# power_side.net
KiCad netlist of a schematic drawn in Altium Designer
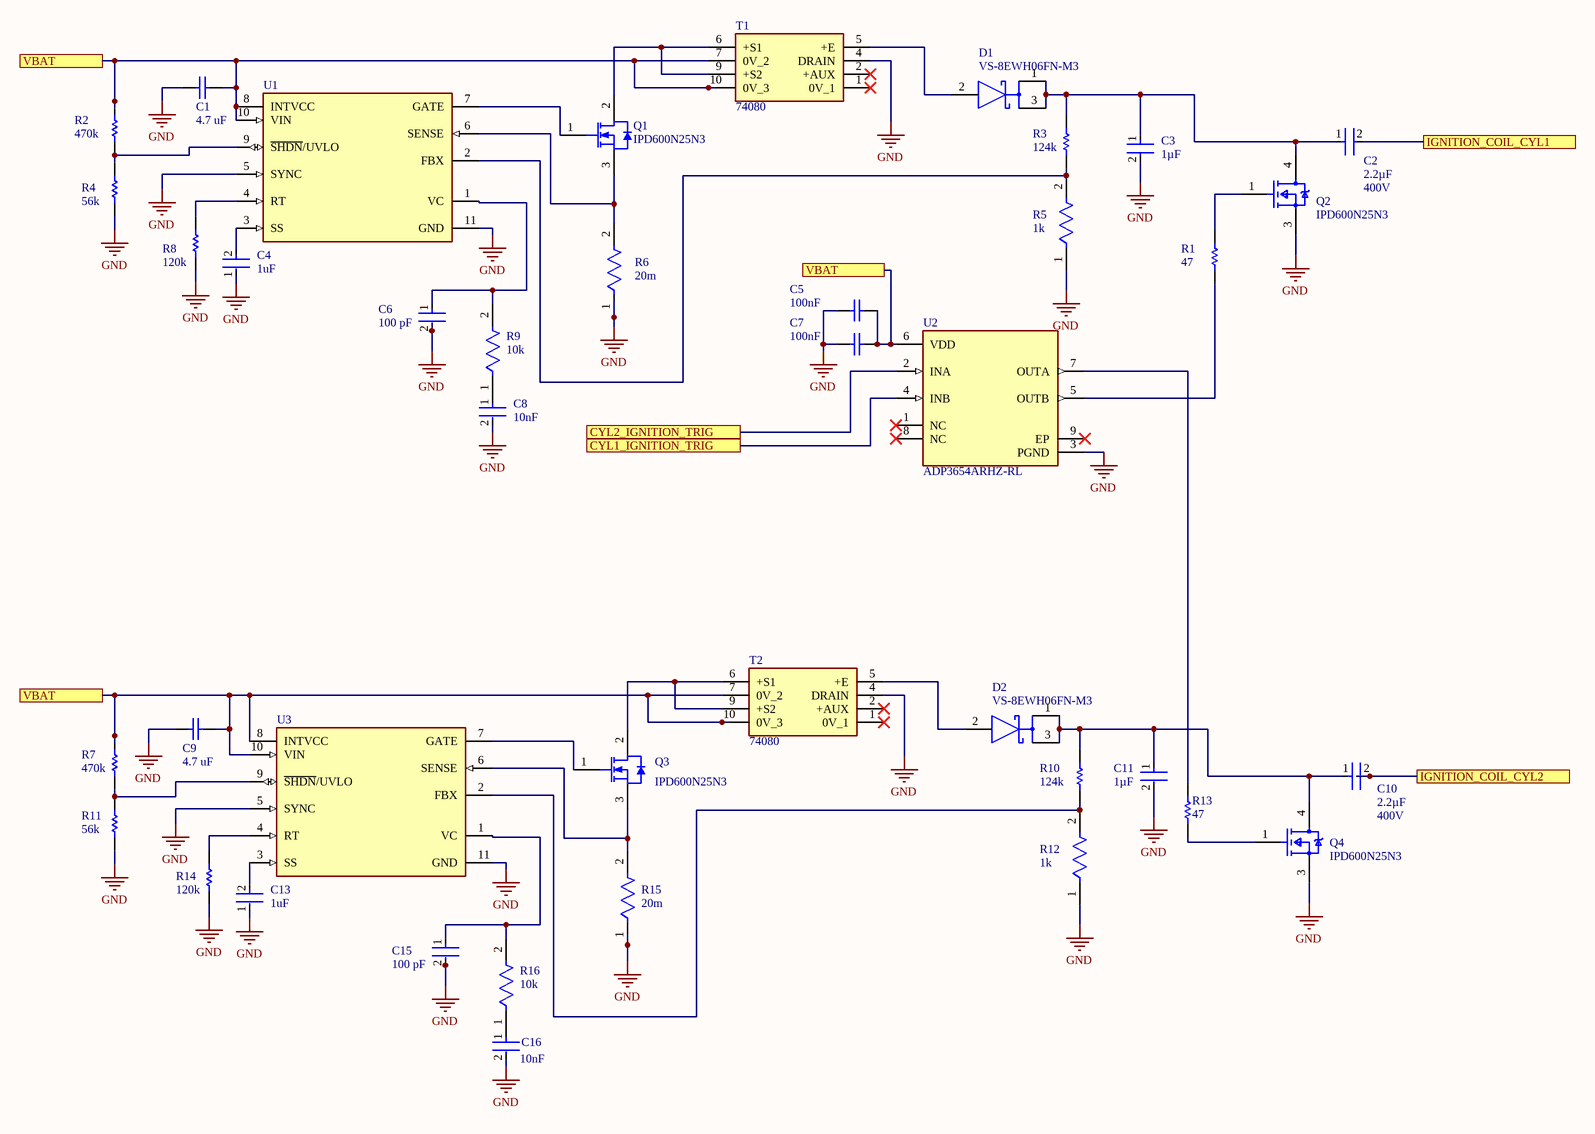
[diagram p0: power_side.SchDoc]

(export (version "E")
  (design (tool "Eeschema 10.0.6"))
  (components
    (comp (ref "C1")
      (value "GRM21BR61C475KA88L")
      (footprint "CAPC2013X135X45LL10T25")
      (description "Chip Capacitor, 4.7 uF, +/- 10%, 16 V, -55 to 85 degC, 0805 (2012 Metric), RoHS, Tape and Reel")
      (fields (field (name "TOLERANCE") "10%") (field (name "CAPACITANCE") "4.7 uF"))
      (libsource (lib "Altium Content Vault") (part "CAP-NP-2"))
    )
    (comp (ref "C2")
      (value "BFC233820225")
      (footprint "FP-BFC233820225-MFG")
      (description "BFC233820225 Film Capacitor, Polypropylene, 800V, 20% +Tol, 20% -Tol, 0.22uF, Through Hole Mount")
      (fields
        (field (name "VOLTAGE RATING (AC)") "400V")
        (field (name "CAPACITANCE") "2.2µF")
        (field (name "TOLERANCE") "20%")
      )
      (libsource (lib "Altium Content Vault") (part "02cd4be3c70576c341d710602a673aa"))
    )
    (comp (ref "C3")
      (value "B32672Z4105K000")
      (footprint "FP-B32672Z4105K000-MFG")
      (fields (field (name "TOLERANCE") "10%") (field (name "CAPACITANCE") "1µF"))
      (libsource (lib "Altium Content Vault") (part "11868f565c42a9108669ba33697ecf6"))
    )
    (comp (ref "C4")
      (value "C1608X5R1H105K080AB")
      (footprint "FP-C1608-080-0_1-IPC_B")
      (description "Multilayer Ceramic Capacitors 1μF ±10% 50V X5R SMD 0603")
      (fields
        (field (name "VOLTAGE") "50V")
        (field (name "CAPACITANCE") "1uF")
        (field (name "TOLERANCE") "10%")
      )
      (libsource (lib "Altium Content Vault") (part "236180d848d6139a670b325ea6854c9"))
    )
    (comp (ref "C5")
      (value "100nF")
      (footprint "CAPC1608X90X35LL15T15")
      (fields
        (field (name "MANUFACTURER") "AVX Interconnect / Elco")
        (field (name "PART NUMBER") "06035C104KAT4A")
      )
      (libsource (lib "Altium Content Vault") (part "CAP"))
    )
    (comp (ref "C6")
      (value "CC0603KRX7R9BB101")
      (footprint "FP-CC0603-DA-MFG")
      (description "CAP CER 100PF 50V X7R 0603")
      (fields
        (field (name "TOLERANCE") "0.1")
        (field (name "OCTOPART") "https://octopart.com/cc0603krx7r9bb101-yageo-42334526")
        (field (name "CAPACITANCE") "100 pF")
      )
      (libsource (lib "Altium Content Vault") (part "11868f565c42a9108669ba33697ecf6"))
    )
    (comp (ref "C7")
      (value "100nF")
      (footprint "CAPC1608X87X35NL15T15")
      (fields (field (name "PART NUMBER") "C0603C475K8PACTU") (field (name "MANUFACTURER") "Kemet"))
      (libsource (lib "Altium Content Vault") (part "CAP"))
    )
    (comp (ref "C8")
      (value "06035C103KAT2A")
      (footprint "FP-0603-L_1_6_0_15-W_0_81-MFG")
      (description "General Purpose Ceramic Capacitor, 0603, 10nF, 10%, X7R, 15%, 50V")
      (fields
        (field (name "VOLTAGE") "50V")
        (field (name "CAPACITANCE") "10nF")
        (field (name "TOLERANCE") "10%")
      )
      (libsource (lib "Altium Content Vault") (part "02cd4be3c70576c341d710602a673aa"))
    )
    (comp (ref "C9")
      (value "GRM21BR61C475KA88L")
      (footprint "CAPC2013X135X45LL10T25")
      (description "Chip Capacitor, 4.7 uF, +/- 10%, 16 V, -55 to 85 degC, 0805 (2012 Metric), RoHS, Tape and Reel")
      (fields (field (name "TOLERANCE") "10%") (field (name "CAPACITANCE") "4.7 uF"))
      (libsource (lib "Altium Content Vault") (part "CAP-NP-2"))
    )
    (comp (ref "C10")
      (value "BFC233820225")
      (footprint "FP-BFC233820225-MFG")
      (description "BFC233820225 Film Capacitor, Polypropylene, 800V, 20% +Tol, 20% -Tol, 0.22uF, Through Hole Mount")
      (fields
        (field (name "VOLTAGE RATING (AC)") "400V")
        (field (name "CAPACITANCE") "2.2µF")
        (field (name "TOLERANCE") "20%")
      )
      (libsource (lib "Altium Content Vault") (part "02cd4be3c70576c341d710602a673aa"))
    )
    (comp (ref "C11")
      (value "B32672Z4105K000")
      (footprint "FP-B32672Z4105K000-MFG")
      (fields (field (name "TOLERANCE") "10%") (field (name "CAPACITANCE") "1µF"))
      (libsource (lib "Altium Content Vault") (part "11868f565c42a9108669ba33697ecf6"))
    )
    (comp (ref "C13")
      (value "C1608X5R1H105K080AB")
      (footprint "FP-C1608-080-0_1-IPC_B")
      (description "Multilayer Ceramic Capacitors 1μF ±10% 50V X5R SMD 0603")
      (fields
        (field (name "VOLTAGE") "50V")
        (field (name "CAPACITANCE") "1uF")
        (field (name "TOLERANCE") "10%")
      )
      (libsource (lib "Altium Content Vault") (part "236180d848d6139a670b325ea6854c9"))
    )
    (comp (ref "C15")
      (value "CC0603KRX7R9BB101")
      (footprint "FP-CC0603-DA-MFG")
      (description "CAP CER 100PF 50V X7R 0603")
      (fields
        (field (name "TOLERANCE") "0.1")
        (field (name "OCTOPART") "https://octopart.com/cc0603krx7r9bb101-yageo-42334526")
        (field (name "CAPACITANCE") "100 pF")
      )
      (libsource (lib "Altium Content Vault") (part "11868f565c42a9108669ba33697ecf6"))
    )
    (comp (ref "C16")
      (value "06035C103KAT2A")
      (footprint "FP-0603-L_1_6_0_15-W_0_81-MFG")
      (description "General Purpose Ceramic Capacitor, 0603, 10nF, 10%, X7R, 15%, 50V")
      (fields
        (field (name "VOLTAGE") "50V")
        (field (name "CAPACITANCE") "10nF")
        (field (name "TOLERANCE") "10%")
      )
      (libsource (lib "Altium Content Vault") (part "02cd4be3c70576c341d710602a673aa"))
    )
    (comp (ref "D1")
      (value "C3D03060E")
      (footprint "FP-TO-252-2_v2-MFG")
      (description "DIODE SCHOTTKY 600V 3A TO252-2")
      (fields (field (name "PN") "VS-8EWH06FN-M3"))
      (libsource (lib "Altium Content Vault") (part "28d9654e8ecf1b769ed8fe2ca1197a5"))
    )
    (comp (ref "D2")
      (value "C3D03060E")
      (footprint "FP-TO-252-2_v2-MFG")
      (description "DIODE SCHOTTKY 600V 3A TO252-2")
      (fields (field (name "PN") "VS-8EWH06FN-M3"))
      (libsource (lib "Altium Content Vault") (part "28d9654e8ecf1b769ed8fe2ca1197a5"))
    )
    (comp (ref "Q1")
      (value "IPD600N25N3")
      (footprint "INF-PG-TO252-3-11_A_L")
      (fields (field (name "PARTNUMBER") "IPD035N06L3 G") (field (name "MANUFACTURER") "Infineon"))
      (libsource (lib "Altium Content Vault") (part "INF-NEMOS-GDS-3"))
    )
    (comp (ref "Q2")
      (value "IPD600N25N3")
      (footprint "FP-PG-TO252-3-MFG")
      (description "MOSFET N-CH 30V 161A DPAK")
      (fields
        (field (name "OCTOPART") "https://octopart.com/irlr7843trpbf-infineon-65875062")
        (field (name "MANUFACTURER PART NUMBER") "IRLR7843TRPBF")
      )
      (libsource (lib "Altium Content Vault") (part "2f21c11e83d30f418bb422e5a3b3d11"))
    )
    (comp (ref "Q3")
      (value "IPD600N25N3")
      (footprint "INF-PG-TO252-3-11_A_L")
      (fields (field (name "PARTNUMBER") "IPD035N06L3 G") (field (name "MANUFACTURER") "Infineon"))
      (libsource (lib "Altium Content Vault") (part "INF-NEMOS-GDS-3"))
    )
    (comp (ref "Q4")
      (value "IPD600N25N3")
      (footprint "FP-PG-TO252-3-MFG")
      (description "MOSFET N-CH 30V 161A DPAK")
      (fields
        (field (name "OCTOPART") "https://octopart.com/irlr7843trpbf-infineon-65875062")
        (field (name "MANUFACTURER PART NUMBER") "IRLR7843TRPBF")
      )
      (libsource (lib "Altium Content Vault") (part "2f21c11e83d30f418bb422e5a3b3d11"))
    )
    (comp (ref "R1")
      (value "47")
      (footprint "RESC1609X50X30LL10T20")
      (fields (field (name "MANUFACTURER") "Vishay Dale") (field (name "PART NUMBER") "CRCW060347R0FKEA"))
      (libsource (lib "Altium Content Vault") (part "RES"))
    )
    (comp (ref "R2")
      (value "470k")
      (footprint "RESC1608X55X25ML10T15")
      (description "Chip Resistor, 470 KOhm, +/- 1%, 0.1 W, -55 to 155 degC, 0603 (1608 Metric), RoHS, Tape and Reel")
      (fields (field (name "Comment") "RC0603FR-07470KL"))
      (libsource (lib "Altium Content Vault") (part "RES-2"))
    )
    (comp (ref "R3")
      (value "124k")
      (footprint "RESC1608X55X30LL15T15")
      (fields (field (name "PART NUMBER") "ERJ-3EKF1243V") (field (name "MANUFACTURER") "Panasonic"))
      (libsource (lib "Altium Content Vault") (part "RES"))
    )
    (comp (ref "R4")
      (value "56k")
      (footprint "RESC1608X55X25LL10T15")
      (description "Chip Resistor, 56 KOhm, +/- 1%, 0.1 W, -55 to 155 degC, 0603 (1608 Metric), RoHS, Tape and Reel")
      (fields (field (name "MANUFACTURER") "Yageo") (field (name "TOLERANCE") "1%"))
      (libsource (lib "Altium Content Vault") (part "RES-2"))
    )
    (comp (ref "R5")
      (value "1k")
      (footprint "FP-RC0603-0_55-IPC_C")
      (description "RES 1K OHM 1% 1/10W 0603")
      (fields (field (name "TOLERANCE") "1%") (field (name "Comment") "RC0603FR-071KL"))
      (libsource (lib "Altium Content Vault") (part "1029c3af85768c4190bb7ad29bc67b5"))
    )
    (comp (ref "R6")
      (value "20m")
      (footprint "FP-CRA2512-MFG")
      (description "RES 0.02 OHM 1% 3W 2512")
      (fields (field (name "Comment") "CRA2512-FZ-R020ELF"))
      (libsource (lib "Altium Content Vault") (part "1029c3af85768c4190bb7ad29bc67b5"))
    )
    (comp (ref "R7")
      (value "470k")
      (footprint "RESC1608X55X25ML10T15")
      (description "Chip Resistor, 470 KOhm, +/- 1%, 0.1 W, -55 to 155 degC, 0603 (1608 Metric), RoHS, Tape and Reel")
      (fields (field (name "Comment") "RC0603FR-07470KL"))
      (libsource (lib "Altium Content Vault") (part "RES-2"))
    )
    (comp (ref "R8")
      (value "120k")
      (footprint "RESC1608X55X25NL10T15")
      (description "Chip Resistor, 120 KOhm, +/- 1%, 100 mW, -55 to 155 degC, 0603 (1608 Metric), RoHS, Tape and Reel")
      (fields (field (name "TOLERANCE") "10%") (field (name "Comment") "RC0603FR-07120KL"))
      (libsource (lib "Altium Content Vault") (part "RES-2"))
    )
    (comp (ref "R9")
      (value "RC0603FR-0710KL")
      (footprint "FP-RC0603-0_55-IPC_C")
      (description "RES 10K OHM 1% 1/10W 0603")
      (fields (field (name "TOLERANCE") "1%") (field (name "RESISTANCE") "10k"))
      (libsource (lib "Altium Content Vault") (part "1029c3af85768c4190bb7ad29bc67b5"))
    )
    (comp (ref "R10")
      (value "124k")
      (footprint "RESC1608X55X30LL15T15")
      (fields (field (name "PART NUMBER") "ERJ-3EKF1243V") (field (name "MANUFACTURER") "Panasonic"))
      (libsource (lib "Altium Content Vault") (part "RES"))
    )
    (comp (ref "R11")
      (value "RC0603FR-0756KL")
      (footprint "RESC1608X55X25LL10T15")
      (description "Chip Resistor, 56 KOhm, +/- 1%, 0.1 W, -55 to 155 degC, 0603 (1608 Metric), RoHS, Tape and Reel")
      (fields
        (field (name "MANUFACTURER") "Yageo")
        (field (name "RESISTANCE") "56k")
        (field (name "TOLERANCE") "1%")
      )
      (libsource (lib "Altium Content Vault") (part "RES-2"))
    )
    (comp (ref "R12")
      (value "1k")
      (footprint "FP-RC0603-0_55-IPC_C")
      (description "RES 1K OHM 1% 1/10W 0603")
      (fields (field (name "TOLERANCE") "1%") (field (name "Comment") "RC0603FR-071KL"))
      (libsource (lib "Altium Content Vault") (part "1029c3af85768c4190bb7ad29bc67b5"))
    )
    (comp (ref "R13")
      (value "47")
      (footprint "RESC1609X50X30LL10T20")
      (fields (field (name "MANUFACTURER") "Vishay Dale") (field (name "PART NUMBER") "CRCW060347R0FKEA"))
      (libsource (lib "Altium Content Vault") (part "RES"))
    )
    (comp (ref "R14")
      (value "120k")
      (footprint "RESC1608X55X25NL10T15")
      (description "Chip Resistor, 120 KOhm, +/- 1%, 100 mW, -55 to 155 degC, 0603 (1608 Metric), RoHS, Tape and Reel")
      (fields (field (name "TOLERANCE") "10%") (field (name "Comment") "RC0603FR-07120KL"))
      (libsource (lib "Altium Content Vault") (part "RES-2"))
    )
    (comp (ref "R15")
      (value "20m")
      (footprint "FP-CRA2512-MFG")
      (description "RES 0.02 OHM 1% 3W 2512")
      (fields (field (name "Comment") "CRA2512-FZ-R020ELF"))
      (libsource (lib "Altium Content Vault") (part "1029c3af85768c4190bb7ad29bc67b5"))
    )
    (comp (ref "R16")
      (value "RC0603FR-0710KL")
      (footprint "FP-RC0603-0_55-IPC_C")
      (description "RES 10K OHM 1% 1/10W 0603")
      (fields (field (name "TOLERANCE") "1%") (field (name "RESISTANCE") "10k"))
      (libsource (lib "Altium Content Vault") (part "1029c3af85768c4190bb7ad29bc67b5"))
    )
    (comp (ref "T1")
      (value "74080")
      (footprint "SamacSys:74080")
      (description "Transformer")
      (libsource (lib "*") (part "74080"))
    )
    (comp (ref "T2")
      (value "74080")
      (footprint "SamacSys:74080")
      (description "Transformer")
      (libsource (lib "*") (part "74080"))
    )
    (comp (ref "U1")
      (value "LT3758EDD#PBF")
      (footprint "FP-DD-10-05-08-1699-IPC_B")
      (description "IC REG CTRLR MULT TOPOLOGY 10DFN")
      (libsource (lib "Altium Content Vault") (part "079e3863d39c5e5796f69dc810f510e"))
    )
    (comp (ref "U2")
      (value "ADP3654ARHZ-RL")
      (footprint "FP-RH-8-1-IPC_C")
      (description "IC GATE DRVR LOW-SIDE 8MINISOIC")
      (libsource (lib "Altium Content Vault") (part "30ea4086147ff647bd0a3436ecf34e5"))
    )
    (comp (ref "U3")
      (value "LT3758EDD#PBF")
      (footprint "FP-DD-10-05-08-1699-IPC_B")
      (description "IC REG CTRLR MULT TOPOLOGY 10DFN")
      (libsource (lib "Altium Content Vault") (part "079e3863d39c5e5796f69dc810f510e"))
    )
  )
  (nets
    (net (code "1") (name "/CYL1_IGNITION_TRIG") (class "Default")
      (node (ref "U2") (pin "4") (pinfunction "INB_4") (pintype "input"))
    )
    (net (code "2") (name "/CYL2_IGNITION_TRIG") (class "Default")
      (node (ref "U2") (pin "2") (pinfunction "INA_2") (pintype "input"))
    )
    (net (code "3") (name "/IGNITION_COIL_CYL1") (class "Default")
      (node (ref "C2") (pin "2") (pinfunction "2_2") (pintype "passive"))
    )
    (net (code "4") (name "/IGNITION_COIL_CYL2") (class "Default")
      (node (ref "C10") (pin "2") (pinfunction "2_2") (pintype "passive"))
    )
    (net (code "5") (name "/VBAT") (class "Default")
      (node (ref "C1") (pin "2") (pinfunction "2_2") (pintype "passive"))
      (node (ref "C5") (pin "1") (pinfunction "1_1") (pintype "passive"))
      (node (ref "C7") (pin "2") (pinfunction "2_2") (pintype "passive"))
      (node (ref "C9") (pin "2") (pinfunction "2_2") (pintype "passive"))
      (node (ref "R2") (pin "2") (pinfunction "2_2") (pintype "passive"))
      (node (ref "R7") (pin "2") (pinfunction "2_2") (pintype "passive"))
      (node (ref "T1") (pin "10") (pinfunction "0V_3_10") (pintype "passive"))
      (node (ref "T1") (pin "7") (pinfunction "0V_2_7") (pintype "passive"))
      (node (ref "T2") (pin "10") (pinfunction "0V_3_10") (pintype "passive"))
      (node (ref "T2") (pin "7") (pinfunction "0V_2_7") (pintype "passive"))
      (node (ref "U1") (pin "10") (pinfunction "VIN_10") (pintype "input"))
      (node (ref "U1") (pin "8") (pinfunction "INTVCC_8") (pintype "power_in"))
      (node (ref "U2") (pin "6") (pinfunction "VDD_6") (pintype "power_in"))
      (node (ref "U3") (pin "10") (pinfunction "VIN_10") (pintype "input"))
      (node (ref "U3") (pin "8") (pinfunction "INTVCC_8") (pintype "power_in"))
    )
    (net (code "6") (name "GND") (class "Default")
      (node (ref "C1") (pin "1") (pinfunction "1_1") (pintype "passive"))
      (node (ref "C11") (pin "2") (pinfunction "2_2") (pintype "passive"))
      (node (ref "C13") (pin "1") (pinfunction "1_1") (pintype "passive"))
      (node (ref "C15") (pin "2") (pinfunction "2_2") (pintype "passive"))
      (node (ref "C16") (pin "2") (pinfunction "2_2") (pintype "passive"))
      (node (ref "C3") (pin "2") (pinfunction "2_2") (pintype "passive"))
      (node (ref "C4") (pin "1") (pinfunction "1_1") (pintype "passive"))
      (node (ref "C5") (pin "2") (pinfunction "2_2") (pintype "passive"))
      (node (ref "C6") (pin "2") (pinfunction "2_2") (pintype "passive"))
      (node (ref "C7") (pin "1") (pinfunction "1_1") (pintype "passive"))
      (node (ref "C8") (pin "2") (pinfunction "2_2") (pintype "passive"))
      (node (ref "C9") (pin "1") (pinfunction "1_1") (pintype "passive"))
      (node (ref "Q2") (pin "3") (pinfunction "SOURCE_3") (pintype "passive"))
      (node (ref "Q4") (pin "3") (pinfunction "SOURCE_3") (pintype "passive"))
      (node (ref "R11") (pin "1") (pinfunction "1_1") (pintype "passive"))
      (node (ref "R12") (pin "1") (pinfunction "1_1") (pintype "passive"))
      (node (ref "R14") (pin "1") (pinfunction "1_1") (pintype "passive"))
      (node (ref "R15") (pin "1") (pinfunction "1_1") (pintype "passive"))
      (node (ref "R4") (pin "1") (pinfunction "1_1") (pintype "passive"))
      (node (ref "R5") (pin "1") (pinfunction "1_1") (pintype "passive"))
      (node (ref "R6") (pin "1") (pinfunction "1_1") (pintype "passive"))
      (node (ref "R8") (pin "1") (pinfunction "1_1") (pintype "passive"))
      (node (ref "T1") (pin "4") (pinfunction "DRAIN_4") (pintype "passive"))
      (node (ref "T2") (pin "4") (pinfunction "DRAIN_4") (pintype "passive"))
      (node (ref "U1") (pin "11") (pinfunction "GND_11") (pintype "power_in"))
      (node (ref "U1") (pin "5") (pinfunction "SYNC_5") (pintype "input"))
      (node (ref "U2") (pin "3") (pinfunction "PGND_3") (pintype "power_in"))
      (node (ref "U3") (pin "11") (pinfunction "GND_11") (pintype "power_in"))
      (node (ref "U3") (pin "5") (pinfunction "SYNC_5") (pintype "input"))
    )
    (net (code "7") (name "Net-(C8-Pad1)") (class "Default")
      (node (ref "C8") (pin "1") (pinfunction "1_1") (pintype "passive"))
      (node (ref "R9") (pin "1") (pinfunction "1_1") (pintype "passive"))
    )
    (net (code "8") (name "Net-(C16-Pad1)") (class "Default")
      (node (ref "C16") (pin "1") (pinfunction "1_1") (pintype "passive"))
      (node (ref "R16") (pin "1") (pinfunction "1_1") (pintype "passive"))
    )
    (net (code "9") (name "Net-(D1-A)") (class "Default")
      (node (ref "D1") (pin "2") (pinfunction "A_2") (pintype "passive"))
      (node (ref "T1") (pin "5") (pinfunction "+E_5") (pintype "passive"))
    )
    (net (code "10") (name "Net-(D2-A)") (class "Default")
      (node (ref "D2") (pin "2") (pinfunction "A_2") (pintype "passive"))
      (node (ref "T2") (pin "5") (pinfunction "+E_5") (pintype "passive"))
    )
    (net (code "11") (name "Net-(Q1-DRAIN)") (class "Default")
      (node (ref "Q1") (pin "2") (pinfunction "DRAIN_2") (pintype "passive"))
      (node (ref "T1") (pin "6") (pinfunction "+S1_6") (pintype "passive"))
      (node (ref "T1") (pin "9") (pinfunction "+S2_9") (pintype "passive"))
    )
    (net (code "12") (name "Net-(Q1-GATE)") (class "Default")
      (node (ref "Q1") (pin "1") (pinfunction "GATE_1") (pintype "passive"))
      (node (ref "U1") (pin "7") (pinfunction "GATE_7") (pintype "passive"))
    )
    (net (code "13") (name "Net-(Q1-SOURCE)") (class "Default")
      (node (ref "Q1") (pin "3") (pinfunction "SOURCE_3") (pintype "passive"))
      (node (ref "R6") (pin "2") (pinfunction "2_2") (pintype "passive"))
      (node (ref "U1") (pin "6") (pinfunction "SENSE_6") (pintype "input"))
    )
    (net (code "14") (name "Net-(Q2-DRAIN)") (class "Default")
      (node (ref "C2") (pin "1") (pinfunction "1_1") (pintype "passive"))
      (node (ref "C3") (pin "1") (pinfunction "1_1") (pintype "passive"))
      (node (ref "D1") (pin "1") (pinfunction "C_1") (pintype "passive"))
      (node (ref "D1") (pin "3") (pinfunction "C_3") (pintype "passive"))
      (node (ref "Q2") (pin "4") (pinfunction "DRAIN_4") (pintype "passive"))
      (node (ref "R3") (pin "2") (pinfunction "2_2") (pintype "passive"))
    )
    (net (code "15") (name "Net-(Q2-GATE)") (class "Default")
      (node (ref "Q2") (pin "1") (pinfunction "GATE_1") (pintype "passive"))
      (node (ref "R1") (pin "2") (pinfunction "2_2") (pintype "passive"))
    )
    (net (code "16") (name "Net-(Q3-DRAIN)") (class "Default")
      (node (ref "Q3") (pin "2") (pinfunction "DRAIN_2") (pintype "passive"))
      (node (ref "T2") (pin "6") (pinfunction "+S1_6") (pintype "passive"))
      (node (ref "T2") (pin "9") (pinfunction "+S2_9") (pintype "passive"))
    )
    (net (code "17") (name "Net-(Q3-GATE)") (class "Default")
      (node (ref "Q3") (pin "1") (pinfunction "GATE_1") (pintype "passive"))
      (node (ref "U3") (pin "7") (pinfunction "GATE_7") (pintype "passive"))
    )
    (net (code "18") (name "Net-(Q3-SOURCE)") (class "Default")
      (node (ref "Q3") (pin "3") (pinfunction "SOURCE_3") (pintype "passive"))
      (node (ref "R15") (pin "2") (pinfunction "2_2") (pintype "passive"))
      (node (ref "U3") (pin "6") (pinfunction "SENSE_6") (pintype "input"))
    )
    (net (code "19") (name "Net-(Q4-DRAIN)") (class "Default")
      (node (ref "C10") (pin "1") (pinfunction "1_1") (pintype "passive"))
      (node (ref "C11") (pin "1") (pinfunction "1_1") (pintype "passive"))
      (node (ref "D2") (pin "1") (pinfunction "C_1") (pintype "passive"))
      (node (ref "D2") (pin "3") (pinfunction "C_3") (pintype "passive"))
      (node (ref "Q4") (pin "4") (pinfunction "DRAIN_4") (pintype "passive"))
      (node (ref "R10") (pin "2") (pinfunction "2_2") (pintype "passive"))
    )
    (net (code "20") (name "Net-(Q4-GATE)") (class "Default")
      (node (ref "Q4") (pin "1") (pinfunction "GATE_1") (pintype "passive"))
      (node (ref "R13") (pin "1") (pinfunction "1_1") (pintype "passive"))
    )
    (net (code "21") (name "Net-(U1-FBX)") (class "Default")
      (node (ref "R3") (pin "1") (pinfunction "1_1") (pintype "passive"))
      (node (ref "R5") (pin "2") (pinfunction "2_2") (pintype "passive"))
      (node (ref "U1") (pin "2") (pinfunction "FBX_2") (pintype "passive"))
    )
    (net (code "22") (name "Net-(U1-RT)") (class "Default")
      (node (ref "R8") (pin "2") (pinfunction "2_2") (pintype "passive"))
      (node (ref "U1") (pin "4") (pinfunction "RT_4") (pintype "input"))
    )
    (net (code "23") (name "Net-(U1-SS)") (class "Default")
      (node (ref "C4") (pin "2") (pinfunction "2_2") (pintype "passive"))
      (node (ref "U1") (pin "3") (pinfunction "SS_3") (pintype "input"))
    )
    (net (code "24") (name "Net-(U1-VC)") (class "Default")
      (node (ref "C6") (pin "1") (pinfunction "1_1") (pintype "passive"))
      (node (ref "R9") (pin "2") (pinfunction "2_2") (pintype "passive"))
      (node (ref "U1") (pin "1") (pinfunction "VC_1") (pintype "passive"))
    )
    (net (code "25") (name "Net-(U1-~{SHDN}{slash}UVLO)") (class "Default")
      (node (ref "R2") (pin "1") (pinfunction "1_1") (pintype "passive"))
      (node (ref "R4") (pin "2") (pinfunction "2_2") (pintype "passive"))
      (node (ref "U1") (pin "9") (pinfunction "~{SHDN}/UVLO_9") (pintype "bidirectional"))
    )
    (net (code "26") (name "Net-(U2-OUTA)") (class "Default")
      (node (ref "R13") (pin "2") (pinfunction "2_2") (pintype "passive"))
      (node (ref "U2") (pin "7") (pinfunction "OUTA_7") (pintype "output"))
    )
    (net (code "27") (name "Net-(U2-OUTB)") (class "Default")
      (node (ref "R1") (pin "1") (pinfunction "1_1") (pintype "passive"))
      (node (ref "U2") (pin "5") (pinfunction "OUTB_5") (pintype "output"))
    )
    (net (code "28") (name "Net-(U3-FBX)") (class "Default")
      (node (ref "R10") (pin "1") (pinfunction "1_1") (pintype "passive"))
      (node (ref "R12") (pin "2") (pinfunction "2_2") (pintype "passive"))
      (node (ref "U3") (pin "2") (pinfunction "FBX_2") (pintype "passive"))
    )
    (net (code "29") (name "Net-(U3-RT)") (class "Default")
      (node (ref "R14") (pin "2") (pinfunction "2_2") (pintype "passive"))
      (node (ref "U3") (pin "4") (pinfunction "RT_4") (pintype "input"))
    )
    (net (code "30") (name "Net-(U3-SS)") (class "Default")
      (node (ref "C13") (pin "2") (pinfunction "2_2") (pintype "passive"))
      (node (ref "U3") (pin "3") (pinfunction "SS_3") (pintype "input"))
    )
    (net (code "31") (name "Net-(U3-VC)") (class "Default")
      (node (ref "C15") (pin "1") (pinfunction "1_1") (pintype "passive"))
      (node (ref "R16") (pin "2") (pinfunction "2_2") (pintype "passive"))
      (node (ref "U3") (pin "1") (pinfunction "VC_1") (pintype "passive"))
    )
    (net (code "32") (name "Net-(U3-~{SHDN}{slash}UVLO)") (class "Default")
      (node (ref "R11") (pin "2") (pinfunction "2_2") (pintype "passive"))
      (node (ref "R7") (pin "1") (pinfunction "1_1") (pintype "passive"))
      (node (ref "U3") (pin "9") (pinfunction "~{SHDN}/UVLO_9") (pintype "bidirectional"))
    )
    (net (code "33") (name "unconnected-(T1-+AUX-Pad2)") (class "Default")
      (node (ref "T1") (pin "2") (pinfunction "+AUX_2") (pintype "passive+no_connect"))
    )
    (net (code "34") (name "unconnected-(T1-0V_1-Pad1)") (class "Default")
      (node (ref "T1") (pin "1") (pinfunction "0V_1_1") (pintype "passive+no_connect"))
    )
    (net (code "35") (name "unconnected-(T2-+AUX-Pad2)") (class "Default")
      (node (ref "T2") (pin "2") (pinfunction "+AUX_2") (pintype "passive+no_connect"))
    )
    (net (code "36") (name "unconnected-(T2-0V_1-Pad1)") (class "Default")
      (node (ref "T2") (pin "1") (pinfunction "0V_1_1") (pintype "passive+no_connect"))
    )
    (net (code "37") (name "unconnected-(U2-EP-Pad9)") (class "Default")
      (node (ref "U2") (pin "9") (pinfunction "EP_9") (pintype "power_in+no_connect"))
    )
    (net (code "38") (name "unconnected-(U2-NC-Pad1)") (class "Default")
      (node (ref "U2") (pin "1") (pinfunction "NC_1") (pintype "passive+no_connect"))
    )
    (net (code "39") (name "unconnected-(U2-NC-Pad8)") (class "Default")
      (node (ref "U2") (pin "8") (pinfunction "NC_8") (pintype "passive+no_connect"))
    )
  )
)
